# ProProject__CW32__2024-02-05.net
KiCad netlist of a schematic drawn in EasyEDA Pro
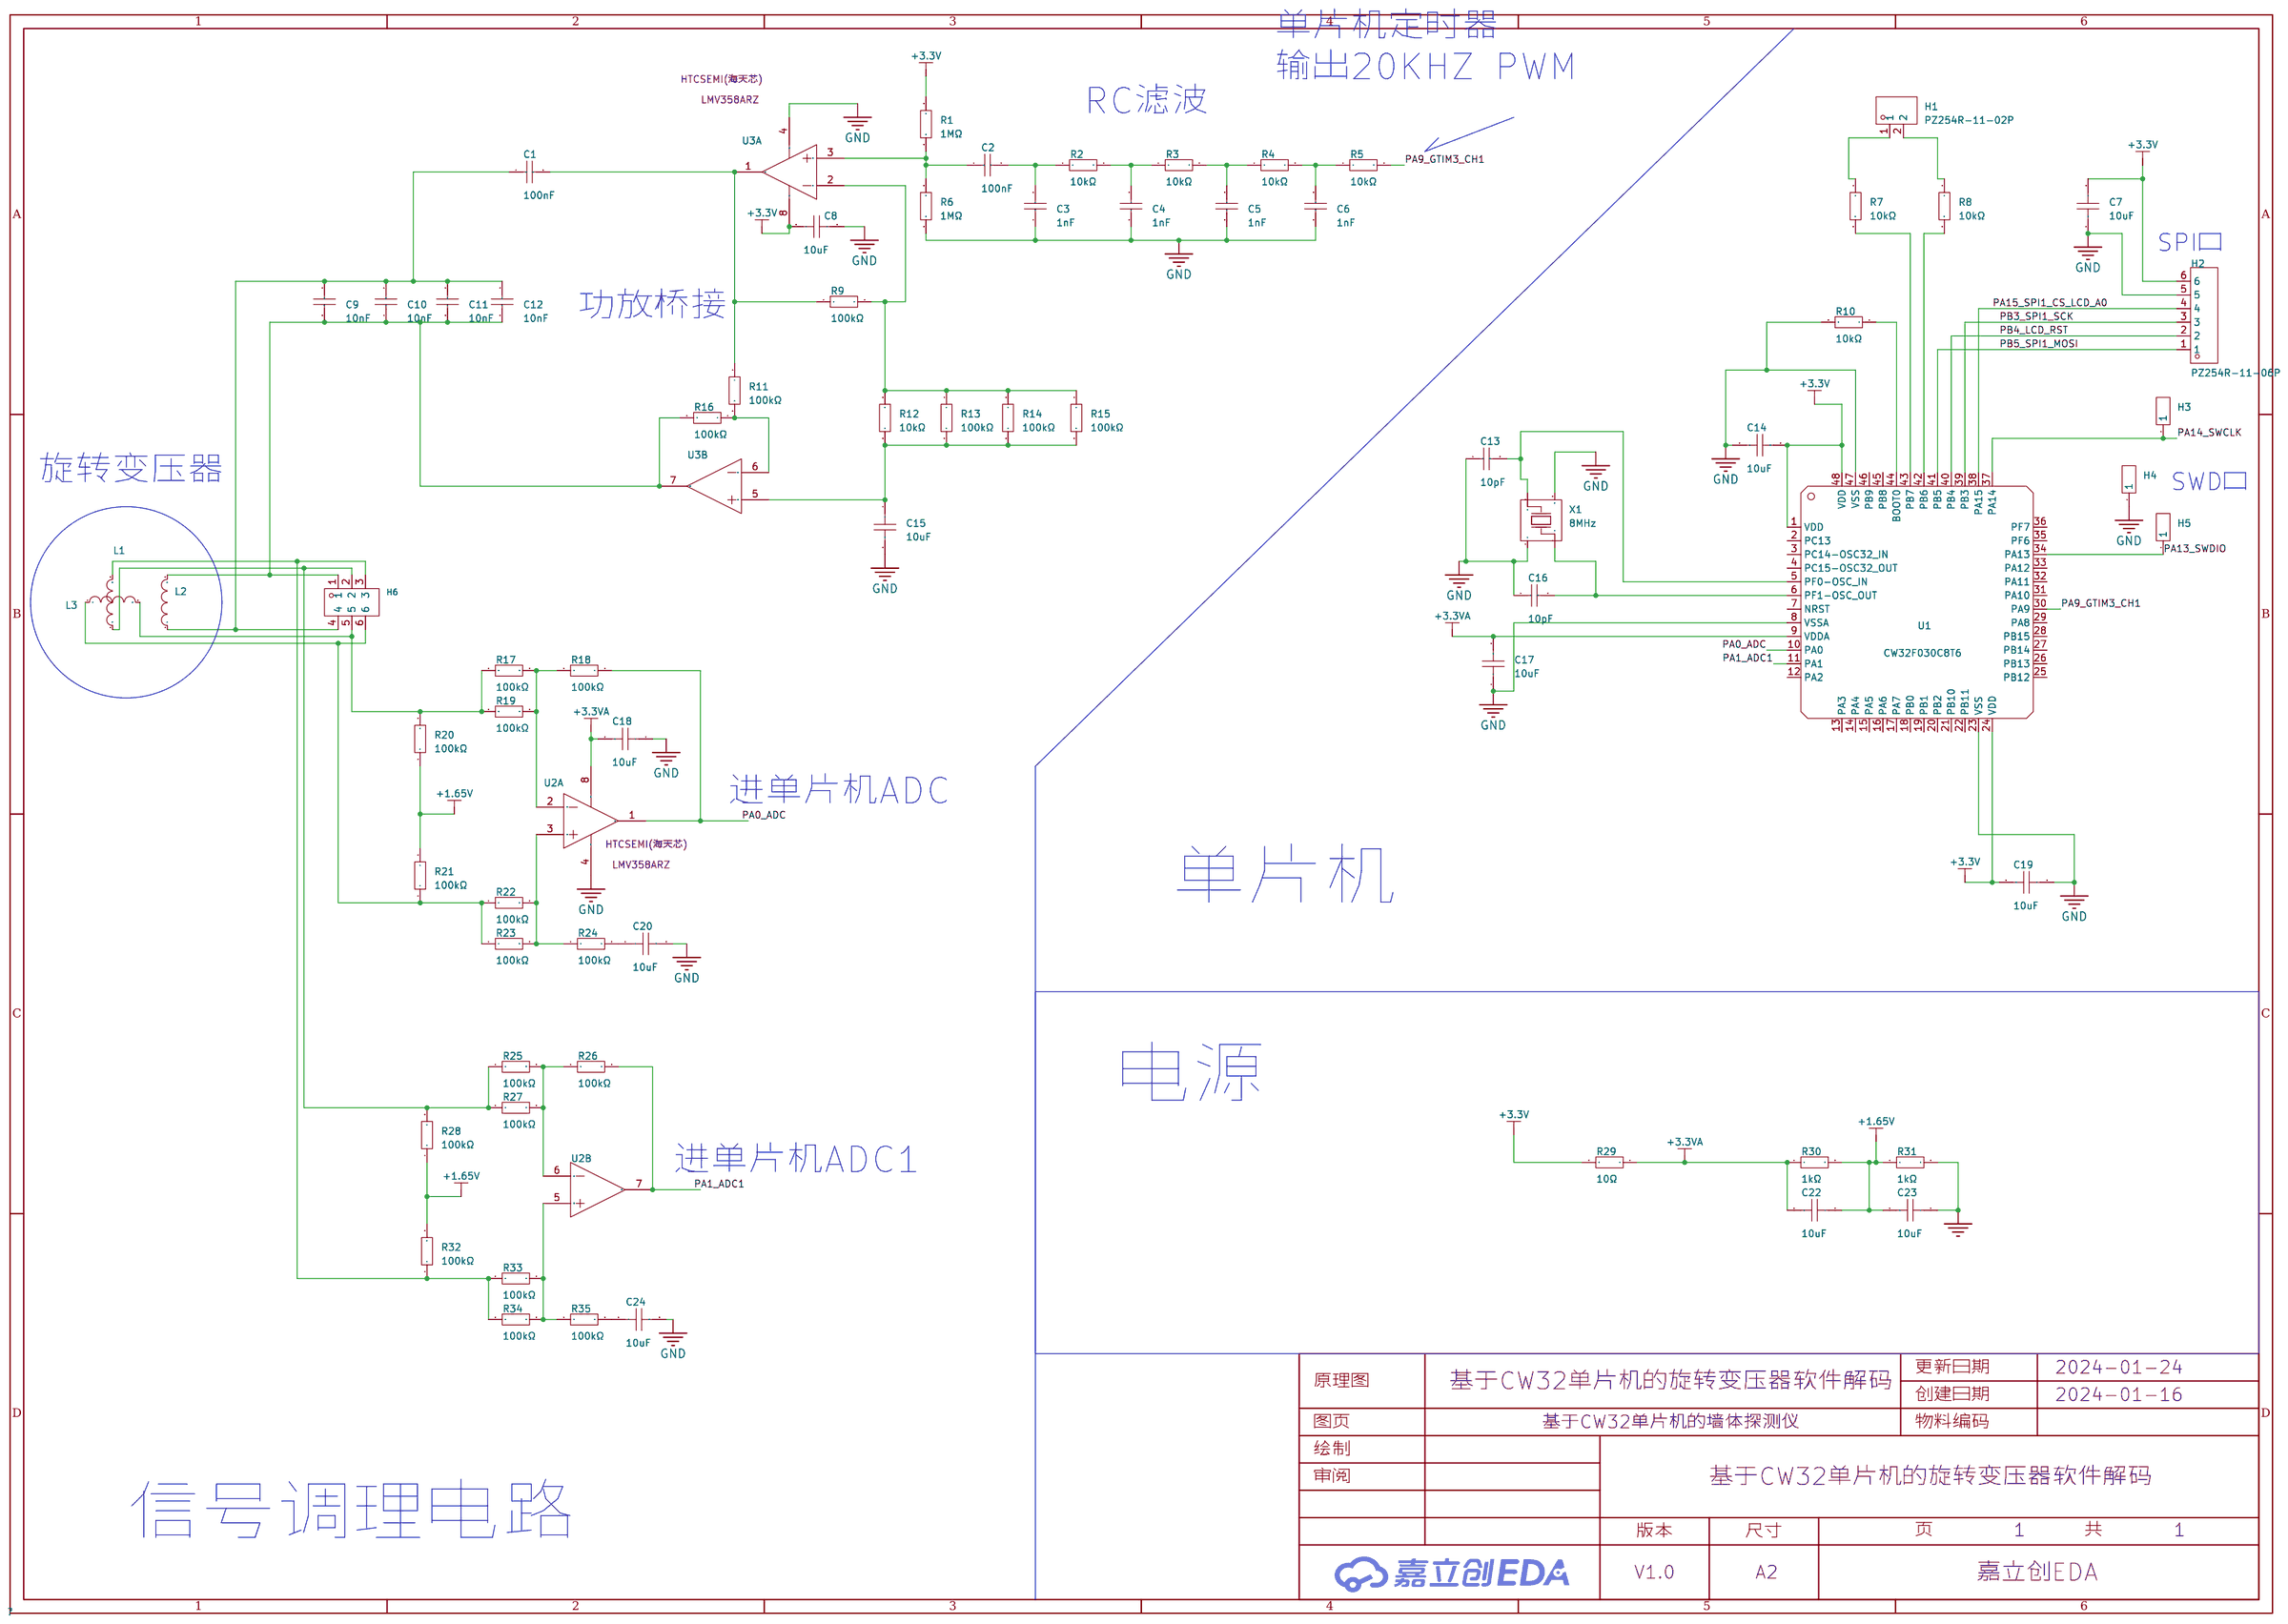
[diagram p0: schematic sheet]

(export (version "E")
  (design (tool "Eeschema 10.0.6"))
  (components
    (comp (ref "C1")
      (value "100nF")
      (footprint "easyedapro:C0603")
      (description "容值:100nF;精度:±10%;额定电压:50V;材质(温度系数):X7R;")
      (fields (field (name "Manufacturer Part") "0603B104K500NT") (field (name "Manufacturer") "FH(风华)"))
      (libsource (lib "easyedapro") (part "0603B104K500NT"))
    )
    (comp (ref "C2")
      (value "100nF")
      (footprint "easyedapro:C0603")
      (description "容值:100nF;精度:±10%;额定电压:50V;材质(温度系数):X7R;")
      (fields (field (name "Manufacturer Part") "0603B104K500NT") (field (name "Manufacturer") "FH(风华)"))
      (libsource (lib "easyedapro") (part "0603B104K500NT"))
    )
    (comp (ref "C3")
      (value "1nF")
      (footprint "easyedapro:C0603")
      (description "容值:1nF;精度:±5%;额定电压:50V;材质(温度系数):NP0;")
      (fields
        (field (name "Manufacturer Part") "CC0603JRNPO9BN102")
        (field (name "Manufacturer") "YAGEO(国巨)")
      )
      (libsource (lib "easyedapro") (part "CC0603JRNPO9BN102"))
    )
    (comp (ref "C4")
      (value "1nF")
      (footprint "easyedapro:C0603")
      (description "容值:1nF;精度:±5%;额定电压:50V;材质(温度系数):NP0;")
      (fields
        (field (name "Manufacturer Part") "CC0603JRNPO9BN102")
        (field (name "Manufacturer") "YAGEO(国巨)")
      )
      (libsource (lib "easyedapro") (part "CC0603JRNPO9BN102"))
    )
    (comp (ref "C5")
      (value "1nF")
      (footprint "easyedapro:C0603")
      (description "容值:1nF;精度:±5%;额定电压:50V;材质(温度系数):NP0;")
      (fields
        (field (name "Manufacturer Part") "CC0603JRNPO9BN102")
        (field (name "Manufacturer") "YAGEO(国巨)")
      )
      (libsource (lib "easyedapro") (part "CC0603JRNPO9BN102"))
    )
    (comp (ref "C6")
      (value "1nF")
      (footprint "easyedapro:C0603")
      (description "容值:1nF;精度:±5%;额定电压:50V;材质(温度系数):NP0;")
      (fields
        (field (name "Manufacturer Part") "CC0603JRNPO9BN102")
        (field (name "Manufacturer") "YAGEO(国巨)")
      )
      (libsource (lib "easyedapro") (part "CC0603JRNPO9BN102"))
    )
    (comp (ref "C7")
      (value "10uF")
      (footprint "easyedapro:C0603")
      (description "容值:10uF;精度:±10%;额定电压:10V;材质(温度系数):X5R;")
      (fields
        (field (name "Manufacturer Part") "CL10A106KP8NNNC")
        (field (name "Manufacturer") "SAMSUNG(三星)")
      )
      (libsource (lib "easyedapro") (part "CL10A106KP8NNNC"))
    )
    (comp (ref "C8")
      (value "10uF")
      (footprint "easyedapro:C0603")
      (description "容值:10uF;精度:±10%;额定电压:10V;材质(温度系数):X5R;")
      (fields
        (field (name "Manufacturer Part") "CL10A106KP8NNNC")
        (field (name "Manufacturer") "SAMSUNG(三星)")
      )
      (libsource (lib "easyedapro") (part "CL10A106KP8NNNC"))
    )
    (comp (ref "C9")
      (value "10nF")
      (footprint "easyedapro:C0603")
      (description "容值:10nF;精度:±10%;额定电压:50V;材质(温度系数):X7R;")
      (fields
        (field (name "Manufacturer Part") "CC0603KRX7R9BB103")
        (field (name "Manufacturer") "YAGEO(国巨)")
      )
      (libsource (lib "easyedapro") (part "CC0603KRX7R9BB103"))
    )
    (comp (ref "C10")
      (value "10nF")
      (footprint "easyedapro:C0603")
      (description "容值:10nF;精度:±10%;额定电压:50V;材质(温度系数):X7R;")
      (fields
        (field (name "Manufacturer Part") "CC0603KRX7R9BB103")
        (field (name "Manufacturer") "YAGEO(国巨)")
      )
      (libsource (lib "easyedapro") (part "CC0603KRX7R9BB103"))
    )
    (comp (ref "C11")
      (value "10nF")
      (footprint "easyedapro:C0603")
      (description "容值:10nF;精度:±10%;额定电压:50V;材质(温度系数):X7R;")
      (fields
        (field (name "Manufacturer Part") "CC0603KRX7R9BB103")
        (field (name "Manufacturer") "YAGEO(国巨)")
      )
      (libsource (lib "easyedapro") (part "CC0603KRX7R9BB103"))
    )
    (comp (ref "C12")
      (value "10nF")
      (footprint "easyedapro:C0603")
      (description "容值:10nF;精度:±10%;额定电压:50V;材质(温度系数):X7R;")
      (fields
        (field (name "Manufacturer Part") "CC0603KRX7R9BB103")
        (field (name "Manufacturer") "YAGEO(国巨)")
      )
      (libsource (lib "easyedapro") (part "CC0603KRX7R9BB103"))
    )
    (comp (ref "C13")
      (value "10pF")
      (footprint "easyedapro:C0603")
      (description "容值:10pF;精度:±5%;额定电压:50V;材质(温度系数):NP0;")
      (fields
        (field (name "Manufacturer Part") "CC0603JRNPO9BN100")
        (field (name "Manufacturer") "YAGEO(国巨)")
      )
      (libsource (lib "easyedapro") (part "CC0603JRNPO9BN100"))
    )
    (comp (ref "C14")
      (value "10uF")
      (footprint "easyedapro:C0603")
      (description "容值:10uF;精度:±10%;额定电压:10V;材质(温度系数):X5R;")
      (fields
        (field (name "Manufacturer Part") "CL10A106KP8NNNC")
        (field (name "Manufacturer") "SAMSUNG(三星)")
      )
      (libsource (lib "easyedapro") (part "CL10A106KP8NNNC"))
    )
    (comp (ref "C15")
      (value "10uF")
      (footprint "easyedapro:C0603")
      (description "容值:10uF;精度:±10%;额定电压:10V;材质(温度系数):X5R;")
      (fields
        (field (name "Manufacturer Part") "CL10A106KP8NNNC")
        (field (name "Manufacturer") "SAMSUNG(三星)")
      )
      (libsource (lib "easyedapro") (part "CL10A106KP8NNNC"))
    )
    (comp (ref "C16")
      (value "10pF")
      (footprint "easyedapro:C0603")
      (description "容值:10pF;精度:±5%;额定电压:50V;材质(温度系数):NP0;")
      (fields
        (field (name "Manufacturer Part") "CC0603JRNPO9BN100")
        (field (name "Manufacturer") "YAGEO(国巨)")
      )
      (libsource (lib "easyedapro") (part "CC0603JRNPO9BN100"))
    )
    (comp (ref "C17")
      (value "10uF")
      (footprint "easyedapro:C0603")
      (description "容值:10uF;精度:±10%;额定电压:10V;材质(温度系数):X5R;")
      (fields
        (field (name "Manufacturer Part") "CL10A106KP8NNNC")
        (field (name "Manufacturer") "SAMSUNG(三星)")
      )
      (libsource (lib "easyedapro") (part "CL10A106KP8NNNC"))
    )
    (comp (ref "C18")
      (value "10uF")
      (footprint "easyedapro:C0603")
      (description "容值:10uF;精度:±10%;额定电压:10V;材质(温度系数):X5R;")
      (fields
        (field (name "Manufacturer Part") "CL10A106KP8NNNC")
        (field (name "Manufacturer") "SAMSUNG(三星)")
      )
      (libsource (lib "easyedapro") (part "CL10A106KP8NNNC"))
    )
    (comp (ref "C19")
      (value "10uF")
      (footprint "easyedapro:C0603")
      (description "容值:10uF;精度:±10%;额定电压:10V;材质(温度系数):X5R;")
      (fields
        (field (name "Manufacturer Part") "CL10A106KP8NNNC")
        (field (name "Manufacturer") "SAMSUNG(三星)")
      )
      (libsource (lib "easyedapro") (part "CL10A106KP8NNNC"))
    )
    (comp (ref "C20")
      (value "10uF")
      (footprint "easyedapro:C0603")
      (description "容值:10uF;精度:±10%;额定电压:10V;材质(温度系数):X5R;")
      (fields
        (field (name "Manufacturer Part") "CL10A106KP8NNNC")
        (field (name "Manufacturer") "SAMSUNG(三星)")
      )
      (libsource (lib "easyedapro") (part "CL10A106KP8NNNC"))
    )
    (comp (ref "C22")
      (value "10uF")
      (footprint "easyedapro:C0603")
      (description "容值:10uF;精度:±10%;额定电压:10V;材质(温度系数):X5R;")
      (fields
        (field (name "Manufacturer Part") "CL10A106KP8NNNC")
        (field (name "Manufacturer") "SAMSUNG(三星)")
      )
      (libsource (lib "easyedapro") (part "CL10A106KP8NNNC"))
    )
    (comp (ref "C23")
      (value "10uF")
      (footprint "easyedapro:C0603")
      (description "容值:10uF;精度:±10%;额定电压:10V;材质(温度系数):X5R;")
      (fields
        (field (name "Manufacturer Part") "CL10A106KP8NNNC")
        (field (name "Manufacturer") "SAMSUNG(三星)")
      )
      (libsource (lib "easyedapro") (part "CL10A106KP8NNNC"))
    )
    (comp (ref "C24")
      (value "10uF")
      (footprint "easyedapro:C0603")
      (description "容值:10uF;精度:±10%;额定电压:10V;材质(温度系数):X5R;")
      (fields
        (field (name "Manufacturer Part") "CL10A106KP8NNNC")
        (field (name "Manufacturer") "SAMSUNG(三星)")
      )
      (libsource (lib "easyedapro") (part "CL10A106KP8NNNC"))
    )
    (comp (ref "H1")
      (value "PZ254R-11-02P")
      (footprint "easyedapro:HDR-TH_2P-P2.54-H-M-W10.4")
      (fields (field (name "Manufacturer") "XFCN(兴飞)"))
      (libsource (lib "easyedapro") (part "PZ254R-11-02P"))
    )
    (comp (ref "H2")
      (value "PZ254R-11-06P")
      (footprint "easyedapro:HDR-TH_6P-P2.54-H-M-W10.4")
      (fields (field (name "Manufacturer") "XFCN(兴飞)"))
      (libsource (lib "easyedapro") (part "PZ254R-11-06P"))
    )
    (comp (ref "H3")
      (value "~")
      (footprint "easyedapro:HDR-TH_1P-V-M_XKB_X4611WV-01I-C28D40")
      (libsource (lib "easyedapro") (part "HDR_1x1"))
    )
    (comp (ref "H4")
      (value "~")
      (footprint "easyedapro:HDR-TH_1P-V-M_XKB_X4611WV-01I-C28D40")
      (libsource (lib "easyedapro") (part "HDR_1x1"))
    )
    (comp (ref "H5")
      (value "~")
      (footprint "easyedapro:HDR-TH_1P-V-M_XKB_X4611WV-01I-C28D40")
      (libsource (lib "easyedapro") (part "HDR_1x1"))
    )
    (comp (ref "H6")
      (value "PZ254-2-03-Z-8.5")
      (footprint "easyedapro:HDR-TH_6P-P2.54-V-M-R2-C3-S2.54")
      (fields (field (name "Manufacturer") "HCTL(华灿天禄)"))
      (libsource (lib "easyedapro") (part "PZ254-2-03-Z-8.5"))
    )
    (comp (ref "L1")
      (value "10uH")
      (footprint "easyedapro:L1206")
      (libsource (lib "easyedapro") (part "CMI321609VR27KT"))
    )
    (comp (ref "L2")
      (value "6.3uH")
      (footprint "easyedapro:L1206")
      (libsource (lib "easyedapro") (part "CMI321609VR27KT"))
    )
    (comp (ref "L3")
      (value "10uH")
      (footprint "easyedapro:L1206")
      (libsource (lib "easyedapro") (part "CMI321609VR27KT"))
    )
    (comp (ref "R1")
      (value "1MΩ")
      (footprint "easyedapro:R0603")
      (description "电阻类型:厚膜电阻;阻值:1MΩ;精度:±1%;功率:100mW;")
      (fields
        (field (name "Manufacturer Part") "0603WAF1004T5E")
        (field (name "Manufacturer") "UNI-ROYAL(厚声)")
      )
      (libsource (lib "easyedapro") (part "0603WAF1004T5E"))
    )
    (comp (ref "R2")
      (value "10kΩ")
      (footprint "easyedapro:R0603")
      (description "电阻类型:厚膜电阻;阻值:10kΩ;精度:±1%;功率:100mW;")
      (fields (field (name "Manufacturer Part") "RC0603FR-0710KL") (field (name "Manufacturer") "YAGEO(国巨)"))
      (libsource (lib "easyedapro") (part "RC0603FR-0710KL"))
    )
    (comp (ref "R3")
      (value "10kΩ")
      (footprint "easyedapro:R0603")
      (description "电阻类型:厚膜电阻;阻值:10kΩ;精度:±1%;功率:100mW;")
      (fields (field (name "Manufacturer Part") "RC0603FR-0710KL") (field (name "Manufacturer") "YAGEO(国巨)"))
      (libsource (lib "easyedapro") (part "RC0603FR-0710KL"))
    )
    (comp (ref "R4")
      (value "10kΩ")
      (footprint "easyedapro:R0603")
      (description "电阻类型:厚膜电阻;阻值:10kΩ;精度:±1%;功率:100mW;")
      (fields (field (name "Manufacturer Part") "RC0603FR-0710KL") (field (name "Manufacturer") "YAGEO(国巨)"))
      (libsource (lib "easyedapro") (part "RC0603FR-0710KL"))
    )
    (comp (ref "R5")
      (value "10kΩ")
      (footprint "easyedapro:R0603")
      (description "电阻类型:厚膜电阻;阻值:10kΩ;精度:±1%;功率:100mW;")
      (fields (field (name "Manufacturer Part") "RC0603FR-0710KL") (field (name "Manufacturer") "YAGEO(国巨)"))
      (libsource (lib "easyedapro") (part "RC0603FR-0710KL"))
    )
    (comp (ref "R6")
      (value "1MΩ")
      (footprint "easyedapro:R0603")
      (description "电阻类型:厚膜电阻;阻值:1MΩ;精度:±1%;功率:100mW;")
      (fields
        (field (name "Manufacturer Part") "0603WAF1004T5E")
        (field (name "Manufacturer") "UNI-ROYAL(厚声)")
      )
      (libsource (lib "easyedapro") (part "0603WAF1004T5E"))
    )
    (comp (ref "R7")
      (value "10kΩ")
      (footprint "easyedapro:R0603")
      (description "电阻类型:厚膜电阻;阻值:10kΩ;精度:±1%;功率:100mW;")
      (fields (field (name "Manufacturer Part") "RC0603FR-0710KL") (field (name "Manufacturer") "YAGEO(国巨)"))
      (libsource (lib "easyedapro") (part "RC0603FR-0710KL"))
    )
    (comp (ref "R8")
      (value "10kΩ")
      (footprint "easyedapro:R0603")
      (description "电阻类型:厚膜电阻;阻值:10kΩ;精度:±1%;功率:100mW;")
      (fields (field (name "Manufacturer Part") "RC0603FR-0710KL") (field (name "Manufacturer") "YAGEO(国巨)"))
      (libsource (lib "easyedapro") (part "RC0603FR-0710KL"))
    )
    (comp (ref "R9")
      (value "100kΩ")
      (footprint "easyedapro:R0603")
      (description "电阻类型:厚膜电阻;阻值:100kΩ;精度:±1%;功率:100mW;")
      (fields (field (name "Manufacturer Part") "RC0603FR-07100KL") (field (name "Manufacturer") "YAGEO(国巨)"))
      (libsource (lib "easyedapro") (part "RC0603FR-07100KL"))
    )
    (comp (ref "R10")
      (value "10kΩ")
      (footprint "easyedapro:R0603")
      (description "电阻类型:厚膜电阻;阻值:10kΩ;精度:±1%;功率:100mW;")
      (fields (field (name "Manufacturer Part") "RC0603FR-0710KL") (field (name "Manufacturer") "YAGEO(国巨)"))
      (libsource (lib "easyedapro") (part "RC0603FR-0710KL"))
    )
    (comp (ref "R11")
      (value "100kΩ")
      (footprint "easyedapro:R0603")
      (description "电阻类型:厚膜电阻;阻值:100kΩ;精度:±1%;功率:100mW;")
      (fields (field (name "Manufacturer Part") "RC0603FR-07100KL") (field (name "Manufacturer") "YAGEO(国巨)"))
      (libsource (lib "easyedapro") (part "RC0603FR-07100KL"))
    )
    (comp (ref "R12")
      (value "10kΩ")
      (footprint "easyedapro:R0603")
      (description "电阻类型:厚膜电阻;阻值:10kΩ;精度:±1%;功率:100mW;")
      (fields (field (name "Manufacturer Part") "RC0603FR-0710KL") (field (name "Manufacturer") "YAGEO(国巨)"))
      (libsource (lib "easyedapro") (part "RC0603FR-0710KL"))
    )
    (comp (ref "R13")
      (value "100kΩ")
      (footprint "easyedapro:R0603")
      (description "电阻类型:厚膜电阻;阻值:100kΩ;精度:±1%;功率:100mW;")
      (fields (field (name "Manufacturer Part") "RC0603FR-07100KL") (field (name "Manufacturer") "YAGEO(国巨)"))
      (libsource (lib "easyedapro") (part "RC0603FR-07100KL"))
    )
    (comp (ref "R14")
      (value "100kΩ")
      (footprint "easyedapro:R0603")
      (description "电阻类型:厚膜电阻;阻值:100kΩ;精度:±1%;功率:100mW;")
      (fields (field (name "Manufacturer Part") "RC0603FR-07100KL") (field (name "Manufacturer") "YAGEO(国巨)"))
      (libsource (lib "easyedapro") (part "RC0603FR-07100KL"))
    )
    (comp (ref "R15")
      (value "100kΩ")
      (footprint "easyedapro:R0603")
      (description "电阻类型:厚膜电阻;阻值:100kΩ;精度:±1%;功率:100mW;")
      (fields (field (name "Manufacturer Part") "RC0603FR-07100KL") (field (name "Manufacturer") "YAGEO(国巨)"))
      (libsource (lib "easyedapro") (part "RC0603FR-07100KL"))
    )
    (comp (ref "R16")
      (value "100kΩ")
      (footprint "easyedapro:R0603")
      (description "电阻类型:厚膜电阻;阻值:100kΩ;精度:±1%;功率:100mW;")
      (fields (field (name "Manufacturer Part") "RC0603FR-07100KL") (field (name "Manufacturer") "YAGEO(国巨)"))
      (libsource (lib "easyedapro") (part "RC0603FR-07100KL"))
    )
    (comp (ref "R17")
      (value "100kΩ")
      (footprint "easyedapro:R0603")
      (description "电阻类型:厚膜电阻;阻值:100kΩ;精度:±1%;功率:100mW;")
      (fields (field (name "Manufacturer Part") "RC0603FR-07100KL") (field (name "Manufacturer") "YAGEO(国巨)"))
      (libsource (lib "easyedapro") (part "RC0603FR-07100KL"))
    )
    (comp (ref "R18")
      (value "100kΩ")
      (footprint "easyedapro:R0603")
      (description "电阻类型:厚膜电阻;阻值:100kΩ;精度:±1%;功率:100mW;")
      (fields (field (name "Manufacturer Part") "RC0603FR-07100KL") (field (name "Manufacturer") "YAGEO(国巨)"))
      (libsource (lib "easyedapro") (part "RC0603FR-07100KL"))
    )
    (comp (ref "R19")
      (value "100kΩ")
      (footprint "easyedapro:R0603")
      (description "电阻类型:厚膜电阻;阻值:100kΩ;精度:±1%;功率:100mW;")
      (fields (field (name "Manufacturer Part") "RC0603FR-07100KL") (field (name "Manufacturer") "YAGEO(国巨)"))
      (libsource (lib "easyedapro") (part "RC0603FR-07100KL"))
    )
    (comp (ref "R20")
      (value "100kΩ")
      (footprint "easyedapro:R0603")
      (description "电阻类型:厚膜电阻;阻值:100kΩ;精度:±1%;功率:100mW;")
      (fields (field (name "Manufacturer Part") "RC0603FR-07100KL") (field (name "Manufacturer") "YAGEO(国巨)"))
      (libsource (lib "easyedapro") (part "RC0603FR-07100KL"))
    )
    (comp (ref "R21")
      (value "100kΩ")
      (footprint "easyedapro:R0603")
      (description "电阻类型:厚膜电阻;阻值:100kΩ;精度:±1%;功率:100mW;")
      (fields (field (name "Manufacturer Part") "RC0603FR-07100KL") (field (name "Manufacturer") "YAGEO(国巨)"))
      (libsource (lib "easyedapro") (part "RC0603FR-07100KL"))
    )
    (comp (ref "R22")
      (value "100kΩ")
      (footprint "easyedapro:R0603")
      (description "电阻类型:厚膜电阻;阻值:100kΩ;精度:±1%;功率:100mW;")
      (fields (field (name "Manufacturer Part") "RC0603FR-07100KL") (field (name "Manufacturer") "YAGEO(国巨)"))
      (libsource (lib "easyedapro") (part "RC0603FR-07100KL"))
    )
    (comp (ref "R23")
      (value "100kΩ")
      (footprint "easyedapro:R0603")
      (description "电阻类型:厚膜电阻;阻值:100kΩ;精度:±1%;功率:100mW;")
      (fields (field (name "Manufacturer Part") "RC0603FR-07100KL") (field (name "Manufacturer") "YAGEO(国巨)"))
      (libsource (lib "easyedapro") (part "RC0603FR-07100KL"))
    )
    (comp (ref "R24")
      (value "100kΩ")
      (footprint "easyedapro:R0603")
      (description "电阻类型:厚膜电阻;阻值:100kΩ;精度:±1%;功率:100mW;")
      (fields (field (name "Manufacturer Part") "RC0603FR-07100KL") (field (name "Manufacturer") "YAGEO(国巨)"))
      (libsource (lib "easyedapro") (part "RC0603FR-07100KL"))
    )
    (comp (ref "R25")
      (value "100kΩ")
      (footprint "easyedapro:R0603")
      (description "电阻类型:厚膜电阻;阻值:100kΩ;精度:±1%;功率:100mW;")
      (fields (field (name "Manufacturer Part") "RC0603FR-07100KL") (field (name "Manufacturer") "YAGEO(国巨)"))
      (libsource (lib "easyedapro") (part "RC0603FR-07100KL"))
    )
    (comp (ref "R26")
      (value "100kΩ")
      (footprint "easyedapro:R0603")
      (description "电阻类型:厚膜电阻;阻值:100kΩ;精度:±1%;功率:100mW;")
      (fields (field (name "Manufacturer Part") "RC0603FR-07100KL") (field (name "Manufacturer") "YAGEO(国巨)"))
      (libsource (lib "easyedapro") (part "RC0603FR-07100KL"))
    )
    (comp (ref "R27")
      (value "100kΩ")
      (footprint "easyedapro:R0603")
      (description "电阻类型:厚膜电阻;阻值:100kΩ;精度:±1%;功率:100mW;")
      (fields (field (name "Manufacturer Part") "RC0603FR-07100KL") (field (name "Manufacturer") "YAGEO(国巨)"))
      (libsource (lib "easyedapro") (part "RC0603FR-07100KL"))
    )
    (comp (ref "R28")
      (value "100kΩ")
      (footprint "easyedapro:R0603")
      (description "电阻类型:厚膜电阻;阻值:100kΩ;精度:±1%;功率:100mW;")
      (fields (field (name "Manufacturer Part") "RC0603FR-07100KL") (field (name "Manufacturer") "YAGEO(国巨)"))
      (libsource (lib "easyedapro") (part "RC0603FR-07100KL"))
    )
    (comp (ref "R29")
      (value "10Ω")
      (footprint "easyedapro:R0603")
      (description "电阻类型:厚膜电阻;阻值:10Ω;精度:±1%;功率:100mW;")
      (fields
        (field (name "Manufacturer Part") "0603WAF100JT5E")
        (field (name "Manufacturer") "UNI-ROYAL(厚声)")
      )
      (libsource (lib "easyedapro") (part "0603WAF100JT5E"))
    )
    (comp (ref "R30")
      (value "1kΩ")
      (footprint "easyedapro:R0603")
      (description "电阻类型:厚膜电阻;阻值:1kΩ;精度:±1%;功率:100mW;")
      (fields (field (name "Manufacturer Part") "RC0603FR-071KL") (field (name "Manufacturer") "YAGEO(国巨)"))
      (libsource (lib "easyedapro") (part "RC0603FR-071KL"))
    )
    (comp (ref "R31")
      (value "1kΩ")
      (footprint "easyedapro:R0603")
      (description "电阻类型:厚膜电阻;阻值:1kΩ;精度:±1%;功率:100mW;")
      (fields (field (name "Manufacturer Part") "RC0603FR-071KL") (field (name "Manufacturer") "YAGEO(国巨)"))
      (libsource (lib "easyedapro") (part "RC0603FR-071KL"))
    )
    (comp (ref "R32")
      (value "100kΩ")
      (footprint "easyedapro:R0603")
      (description "电阻类型:厚膜电阻;阻值:100kΩ;精度:±1%;功率:100mW;")
      (fields (field (name "Manufacturer Part") "RC0603FR-07100KL") (field (name "Manufacturer") "YAGEO(国巨)"))
      (libsource (lib "easyedapro") (part "RC0603FR-07100KL"))
    )
    (comp (ref "R33")
      (value "100kΩ")
      (footprint "easyedapro:R0603")
      (description "电阻类型:厚膜电阻;阻值:100kΩ;精度:±1%;功率:100mW;")
      (fields (field (name "Manufacturer Part") "RC0603FR-07100KL") (field (name "Manufacturer") "YAGEO(国巨)"))
      (libsource (lib "easyedapro") (part "RC0603FR-07100KL"))
    )
    (comp (ref "R34")
      (value "100kΩ")
      (footprint "easyedapro:R0603")
      (description "电阻类型:厚膜电阻;阻值:100kΩ;精度:±1%;功率:100mW;")
      (fields (field (name "Manufacturer Part") "RC0603FR-07100KL") (field (name "Manufacturer") "YAGEO(国巨)"))
      (libsource (lib "easyedapro") (part "RC0603FR-07100KL"))
    )
    (comp (ref "R35")
      (value "100kΩ")
      (footprint "easyedapro:R0603")
      (description "电阻类型:厚膜电阻;阻值:100kΩ;精度:±1%;功率:100mW;")
      (fields (field (name "Manufacturer Part") "RC0603FR-07100KL") (field (name "Manufacturer") "YAGEO(国巨)"))
      (libsource (lib "easyedapro") (part "RC0603FR-07100KL"))
    )
    (comp (ref "U1")
      (value "CW32F030C8T6")
      (footprint "easyedapro:LQFP-48_L7.0-W7.0-P0.50-LS9.0-TL")
      (fields (field (name "Manufacturer") "CW(芯源)"))
      (libsource (lib "easyedapro") (part "CW32F030C8T6_C3019113"))
    )
    (comp (ref "U2")
      (value "{ManufacturerPart!}")
      (footprint "easyedapro:SOP-8_L4.9-W3.9-P1.27-LS6.0-BL")
      (description "CMOS低功耗双路运算放大器")
      (fields (field (name "Manufacturer Part") "LMV358ARZ") (field (name "Manufacturer") "HTCSEMI(海天芯)"))
      (libsource (lib "easyedapro") (part "LMV358ARZ"))
    )
    (comp (ref "U3")
      (value "{ManufacturerPart!}")
      (footprint "easyedapro:SOP-8_L4.9-W3.9-P1.27-LS6.0-BL")
      (description "CMOS低功耗双路运算放大器")
      (fields (field (name "Manufacturer Part") "LMV358ARZ") (field (name "Manufacturer") "HTCSEMI(海天芯)"))
      (libsource (lib "easyedapro") (part "LMV358ARZ"))
    )
    (comp (ref "X1")
      (value "8MHz")
      (footprint "easyedapro:OSC-SMD_4P-L3.2-W2.5-BL")
      (description "频率:8MHz;负载电容:10pF;频率公差:±10ppm;")
      (fields (field (name "Manufacturer Part") "TAXM8M4RDBCCT2T") (field (name "Manufacturer") "YJX(雅晶鑫)"))
      (libsource (lib "easyedapro") (part "TAXM8M4RDBCCT2T"))
    )
  )
  (nets
    (net (code "1") (name "+1.65V") (class "Default")
      (node (ref "C22") (pin "1") (pinfunction "1_1") (pintype "unspecified"))
      (node (ref "C23") (pin "2") (pinfunction "2_2") (pintype "unspecified"))
      (node (ref "R20") (pin "1") (pinfunction "1_1") (pintype "unspecified"))
      (node (ref "R21") (pin "2") (pinfunction "2_2") (pintype "unspecified"))
      (node (ref "R28") (pin "1") (pinfunction "1_1") (pintype "unspecified"))
      (node (ref "R30") (pin "2") (pinfunction "2_2") (pintype "input"))
      (node (ref "R31") (pin "1") (pinfunction "1_1") (pintype "input"))
      (node (ref "R32") (pin "2") (pinfunction "2_2") (pintype "unspecified"))
    )
    (net (code "2") (name "+3.3V") (class "Default")
      (node (ref "C14") (pin "2") (pinfunction "2_2") (pintype "unspecified"))
      (node (ref "C19") (pin "1") (pinfunction "1_1") (pintype "unspecified"))
      (node (ref "C7") (pin "2") (pinfunction "2_2") (pintype "unspecified"))
      (node (ref "C8") (pin "2") (pinfunction "2_2") (pintype "unspecified"))
      (node (ref "H2") (pin "6") (pinfunction "6_6") (pintype "unspecified"))
      (node (ref "R1") (pin "2") (pinfunction "2_2") (pintype "input"))
      (node (ref "R29") (pin "2") (pinfunction "2_2") (pintype "input"))
      (node (ref "U1") (pin "1") (pinfunction "VDD_1") (pintype "input"))
      (node (ref "U1") (pin "24") (pinfunction "VDD_24") (pintype "input"))
      (node (ref "U1") (pin "48") (pinfunction "VDD_48") (pintype "input"))
      (node (ref "U3") (pin "8") (pinfunction "VCC_8") (pintype "input"))
    )
    (net (code "3") (name "+3.3VA") (class "Default")
      (node (ref "C17") (pin "2") (pinfunction "2_2") (pintype "unspecified"))
      (node (ref "C18") (pin "2") (pinfunction "2_2") (pintype "unspecified"))
      (node (ref "C22") (pin "2") (pinfunction "2_2") (pintype "unspecified"))
      (node (ref "R29") (pin "1") (pinfunction "1_1") (pintype "input"))
      (node (ref "R30") (pin "1") (pinfunction "1_1") (pintype "input"))
      (node (ref "U1") (pin "9") (pinfunction "VDDA_9") (pintype "input"))
      (node (ref "U2") (pin "8") (pinfunction "VCC_8") (pintype "input"))
    )
    (net (code "4") (name "/PA0_ADC") (class "Default")
      (node (ref "R18") (pin "2") (pinfunction "2_2") (pintype "unspecified"))
      (node (ref "U1") (pin "10") (pinfunction "PA0_10") (pintype "input"))
      (node (ref "U2") (pin "1") (pinfunction "OUT_1") (pintype "output"))
    )
    (net (code "5") (name "/PA1_ADC1") (class "Default")
      (node (ref "R26") (pin "2") (pinfunction "2_2") (pintype "unspecified"))
      (node (ref "U1") (pin "11") (pinfunction "PA1_11") (pintype "input"))
      (node (ref "U2") (pin "7") (pinfunction "OUT2_7") (pintype "output"))
    )
    (net (code "6") (name "/PA9_GTIM3_CH1") (class "Default")
      (node (ref "R5") (pin "2") (pinfunction "2_2") (pintype "input"))
      (node (ref "U1") (pin "30") (pinfunction "PA9_30") (pintype "input"))
    )
    (net (code "7") (name "/PA13_SWDIO") (class "Default")
      (node (ref "H5") (pin "1") (pinfunction "1_1") (pintype "unspecified"))
      (node (ref "U1") (pin "34") (pinfunction "PA13_34") (pintype "input"))
    )
    (net (code "8") (name "/PA14_SWCLK") (class "Default")
      (node (ref "H3") (pin "1") (pinfunction "1_1") (pintype "unspecified"))
      (node (ref "U1") (pin "37") (pinfunction "PA14_37") (pintype "input"))
    )
    (net (code "9") (name "/PA15_SPI1_CS_LCD_A0") (class "Default")
      (node (ref "H2") (pin "4") (pinfunction "4_4") (pintype "unspecified"))
      (node (ref "U1") (pin "38") (pinfunction "PA15_38") (pintype "input"))
    )
    (net (code "10") (name "/PB3_SPI1_SCK") (class "Default")
      (node (ref "H2") (pin "3") (pinfunction "3_3") (pintype "unspecified"))
      (node (ref "U1") (pin "39") (pinfunction "PB3_39") (pintype "input"))
    )
    (net (code "11") (name "/PB4_LCD_RST") (class "Default")
      (node (ref "H2") (pin "2") (pinfunction "2_2") (pintype "unspecified"))
      (node (ref "U1") (pin "40") (pinfunction "PB4_40") (pintype "input"))
    )
    (net (code "12") (name "/PB5_SPI1_MOSI") (class "Default")
      (node (ref "H2") (pin "1") (pinfunction "1_1") (pintype "unspecified"))
      (node (ref "U1") (pin "41") (pinfunction "PB5_41") (pintype "input"))
    )
    (net (code "13") (name "GND") (class "Default")
      (node (ref "C13") (pin "1") (pinfunction "1_1") (pintype "input"))
      (node (ref "C14") (pin "1") (pinfunction "1_1") (pintype "unspecified"))
      (node (ref "C15") (pin "2") (pinfunction "2_2") (pintype "unspecified"))
      (node (ref "C16") (pin "1") (pinfunction "1_1") (pintype "input"))
      (node (ref "C17") (pin "1") (pinfunction "1_1") (pintype "unspecified"))
      (node (ref "C18") (pin "1") (pinfunction "1_1") (pintype "unspecified"))
      (node (ref "C19") (pin "2") (pinfunction "2_2") (pintype "unspecified"))
      (node (ref "C20") (pin "2") (pinfunction "2_2") (pintype "unspecified"))
      (node (ref "C23") (pin "1") (pinfunction "1_1") (pintype "unspecified"))
      (node (ref "C24") (pin "2") (pinfunction "2_2") (pintype "unspecified"))
      (node (ref "C3") (pin "1") (pinfunction "1_1") (pintype "input"))
      (node (ref "C4") (pin "1") (pinfunction "1_1") (pintype "input"))
      (node (ref "C5") (pin "1") (pinfunction "1_1") (pintype "input"))
      (node (ref "C6") (pin "1") (pinfunction "1_1") (pintype "input"))
      (node (ref "C7") (pin "1") (pinfunction "1_1") (pintype "unspecified"))
      (node (ref "C8") (pin "1") (pinfunction "1_1") (pintype "unspecified"))
      (node (ref "H2") (pin "5") (pinfunction "5_5") (pintype "unspecified"))
      (node (ref "H4") (pin "1") (pinfunction "1_1") (pintype "unspecified"))
      (node (ref "R10") (pin "2") (pinfunction "2_2") (pintype "input"))
      (node (ref "R31") (pin "2") (pinfunction "2_2") (pintype "input"))
      (node (ref "R6") (pin "1") (pinfunction "1_1") (pintype "input"))
      (node (ref "U1") (pin "23") (pinfunction "VSS_23") (pintype "input"))
      (node (ref "U1") (pin "47") (pinfunction "VSS_47") (pintype "input"))
      (node (ref "U1") (pin "8") (pinfunction "VSSA_8") (pintype "input"))
      (node (ref "U2") (pin "4") (pinfunction "GND_4") (pintype "input"))
      (node (ref "U3") (pin "4") (pinfunction "GND_4") (pintype "input"))
      (node (ref "X1") (pin "2") (pinfunction "2_2") (pintype "input"))
      (node (ref "X1") (pin "4") (pinfunction "4_4") (pintype "input"))
    )
    (net (code "14") (name "Net-(C1-Pad1)") (class "Default")
      (node (ref "C1") (pin "1") (pinfunction "1_1") (pintype "input"))
      (node (ref "C10") (pin "2") (pinfunction "2_2") (pintype "input"))
      (node (ref "C11") (pin "2") (pinfunction "2_2") (pintype "input"))
      (node (ref "C12") (pin "2") (pinfunction "2_2") (pintype "input"))
      (node (ref "C9") (pin "2") (pinfunction "2_2") (pintype "input"))
      (node (ref "H6") (pin "4") (pinfunction "4_4") (pintype "input"))
      (node (ref "L2") (pin "1") (pinfunction "1_1") (pintype "input"))
    )
    (net (code "15") (name "Net-(C2-Pad2)") (class "Default")
      (node (ref "C2") (pin "2") (pinfunction "2_2") (pintype "input"))
      (node (ref "C3") (pin "2") (pinfunction "2_2") (pintype "input"))
      (node (ref "R2") (pin "1") (pinfunction "1_1") (pintype "input"))
    )
    (net (code "16") (name "Net-(C4-Pad2)") (class "Default")
      (node (ref "C4") (pin "2") (pinfunction "2_2") (pintype "input"))
      (node (ref "R2") (pin "2") (pinfunction "2_2") (pintype "input"))
      (node (ref "R3") (pin "1") (pinfunction "1_1") (pintype "input"))
    )
    (net (code "17") (name "Net-(C5-Pad2)") (class "Default")
      (node (ref "C5") (pin "2") (pinfunction "2_2") (pintype "input"))
      (node (ref "R3") (pin "2") (pinfunction "2_2") (pintype "input"))
      (node (ref "R4") (pin "1") (pinfunction "1_1") (pintype "input"))
    )
    (net (code "18") (name "Net-(C6-Pad2)") (class "Default")
      (node (ref "C6") (pin "2") (pinfunction "2_2") (pintype "input"))
      (node (ref "R4") (pin "2") (pinfunction "2_2") (pintype "input"))
      (node (ref "R5") (pin "1") (pinfunction "1_1") (pintype "input"))
    )
    (net (code "19") (name "Net-(C20-Pad1)") (class "Default")
      (node (ref "C20") (pin "1") (pinfunction "1_1") (pintype "unspecified"))
      (node (ref "R24") (pin "2") (pinfunction "2_2") (pintype "unspecified"))
    )
    (net (code "20") (name "Net-(C24-Pad1)") (class "Default")
      (node (ref "C24") (pin "1") (pinfunction "1_1") (pintype "unspecified"))
      (node (ref "R35") (pin "2") (pinfunction "2_2") (pintype "unspecified"))
    )
    (net (code "21") (name "Net-(H1-Pad1)") (class "Default")
      (node (ref "H1") (pin "1") (pinfunction "1_1") (pintype "unspecified"))
      (node (ref "R7") (pin "1") (pinfunction "1_1") (pintype "input"))
    )
    (net (code "22") (name "Net-(H1-Pad2)") (class "Default")
      (node (ref "H1") (pin "2") (pinfunction "2_2") (pintype "unspecified"))
      (node (ref "R8") (pin "1") (pinfunction "1_1") (pintype "input"))
    )
    (net (code "23") (name "Net-(H6-Pad2)") (class "Default")
      (node (ref "H6") (pin "2") (pinfunction "2_2") (pintype "input"))
      (node (ref "L1") (pin "1") (pinfunction "1_1") (pintype "input"))
      (node (ref "R25") (pin "1") (pinfunction "1_1") (pintype "unspecified"))
      (node (ref "R27") (pin "1") (pinfunction "1_1") (pintype "unspecified"))
      (node (ref "R28") (pin "2") (pinfunction "2_2") (pintype "unspecified"))
    )
    (net (code "24") (name "Net-(H6-Pad3)") (class "Default")
      (node (ref "H6") (pin "3") (pinfunction "3_3") (pintype "input"))
      (node (ref "L1") (pin "2") (pinfunction "2_2") (pintype "input"))
      (node (ref "R32") (pin "1") (pinfunction "1_1") (pintype "unspecified"))
      (node (ref "R33") (pin "1") (pinfunction "1_1") (pintype "unspecified"))
      (node (ref "R34") (pin "1") (pinfunction "1_1") (pintype "unspecified"))
    )
    (net (code "25") (name "Net-(H6-Pad5)") (class "Default")
      (node (ref "H6") (pin "5") (pinfunction "5_5") (pintype "input"))
      (node (ref "L3") (pin "2") (pinfunction "2_2") (pintype "input"))
      (node (ref "R17") (pin "1") (pinfunction "1_1") (pintype "unspecified"))
      (node (ref "R19") (pin "1") (pinfunction "1_1") (pintype "unspecified"))
      (node (ref "R20") (pin "2") (pinfunction "2_2") (pintype "unspecified"))
    )
    (net (code "26") (name "Net-(H6-Pad6)") (class "Default")
      (node (ref "H6") (pin "6") (pinfunction "6_6") (pintype "input"))
      (node (ref "L3") (pin "1") (pinfunction "1_1") (pintype "input"))
      (node (ref "R21") (pin "1") (pinfunction "1_1") (pintype "unspecified"))
      (node (ref "R22") (pin "1") (pinfunction "1_1") (pintype "unspecified"))
      (node (ref "R23") (pin "1") (pinfunction "1_1") (pintype "unspecified"))
    )
    (net (code "27") (name "Net-(U1-BOOT0)") (class "Default")
      (node (ref "R10") (pin "1") (pinfunction "1_1") (pintype "input"))
      (node (ref "U1") (pin "44") (pinfunction "BOOT0_44") (pintype "input"))
    )
    (net (code "28") (name "Net-(U1-PB6)") (class "Default")
      (node (ref "R8") (pin "2") (pinfunction "2_2") (pintype "input"))
      (node (ref "U1") (pin "42") (pinfunction "PB6_42") (pintype "input"))
    )
    (net (code "29") (name "Net-(U1-PB7)") (class "Default")
      (node (ref "R7") (pin "2") (pinfunction "2_2") (pintype "input"))
      (node (ref "U1") (pin "43") (pinfunction "PB7_43") (pintype "input"))
    )
    (net (code "30") (name "Net-(U1-PF0-OSC_IN)") (class "Default")
      (node (ref "C13") (pin "2") (pinfunction "2_2") (pintype "input"))
      (node (ref "U1") (pin "5") (pinfunction "PF0-OSC_IN_5") (pintype "input"))
      (node (ref "X1") (pin "3") (pinfunction "3_3") (pintype "input"))
    )
    (net (code "31") (name "Net-(U1-PF1-OSC_OUT)") (class "Default")
      (node (ref "C16") (pin "2") (pinfunction "2_2") (pintype "input"))
      (node (ref "U1") (pin "6") (pinfunction "PF1-OSC_OUT_6") (pintype "input"))
      (node (ref "X1") (pin "1") (pinfunction "1_1") (pintype "input"))
    )
    (net (code "32") (name "Net-(U2A-IN1+)") (class "Default")
      (node (ref "R22") (pin "2") (pinfunction "2_2") (pintype "unspecified"))
      (node (ref "R23") (pin "2") (pinfunction "2_2") (pintype "unspecified"))
      (node (ref "R24") (pin "1") (pinfunction "1_1") (pintype "unspecified"))
      (node (ref "U2") (pin "3") (pinfunction "IN1+_3") (pintype "input"))
    )
    (net (code "33") (name "Net-(U2A-IN1-)") (class "Default")
      (node (ref "R17") (pin "2") (pinfunction "2_2") (pintype "unspecified"))
      (node (ref "R18") (pin "1") (pinfunction "1_1") (pintype "unspecified"))
      (node (ref "R19") (pin "2") (pinfunction "2_2") (pintype "unspecified"))
      (node (ref "U2") (pin "2") (pinfunction "IN1-_2") (pintype "input"))
    )
    (net (code "34") (name "Net-(U2B-IN2+)") (class "Default")
      (node (ref "R33") (pin "2") (pinfunction "2_2") (pintype "unspecified"))
      (node (ref "R34") (pin "2") (pinfunction "2_2") (pintype "unspecified"))
      (node (ref "R35") (pin "1") (pinfunction "1_1") (pintype "unspecified"))
      (node (ref "U2") (pin "5") (pinfunction "IN2+_5") (pintype "input"))
    )
    (net (code "35") (name "Net-(U2B-IN2-)") (class "Default")
      (node (ref "R25") (pin "2") (pinfunction "2_2") (pintype "unspecified"))
      (node (ref "R26") (pin "1") (pinfunction "1_1") (pintype "unspecified"))
      (node (ref "R27") (pin "2") (pinfunction "2_2") (pintype "unspecified"))
      (node (ref "U2") (pin "6") (pinfunction "IN2-_6") (pintype "input"))
    )
    (net (code "36") (name "Net-(U3A-IN1+)") (class "Default")
      (node (ref "C2") (pin "1") (pinfunction "1_1") (pintype "input"))
      (node (ref "R1") (pin "1") (pinfunction "1_1") (pintype "input"))
      (node (ref "R6") (pin "2") (pinfunction "2_2") (pintype "input"))
      (node (ref "U3") (pin "3") (pinfunction "IN1+_3") (pintype "input"))
    )
    (net (code "37") (name "Net-(U3A-IN1-)") (class "Default")
      (node (ref "R12") (pin "2") (pinfunction "2_2") (pintype "input"))
      (node (ref "R13") (pin "1") (pinfunction "1_1") (pintype "unspecified"))
      (node (ref "R14") (pin "1") (pinfunction "1_1") (pintype "unspecified"))
      (node (ref "R15") (pin "1") (pinfunction "1_1") (pintype "unspecified"))
      (node (ref "R9") (pin "2") (pinfunction "2_2") (pintype "unspecified"))
      (node (ref "U3") (pin "2") (pinfunction "IN1-_2") (pintype "input"))
    )
    (net (code "38") (name "Net-(U3A-OUT)") (class "Default")
      (node (ref "C1") (pin "2") (pinfunction "2_2") (pintype "input"))
      (node (ref "R11") (pin "1") (pinfunction "1_1") (pintype "unspecified"))
      (node (ref "R9") (pin "1") (pinfunction "1_1") (pintype "unspecified"))
      (node (ref "U3") (pin "1") (pinfunction "OUT_1") (pintype "output"))
    )
    (net (code "39") (name "Net-(U3B-IN2+)") (class "Default")
      (node (ref "C15") (pin "1") (pinfunction "1_1") (pintype "unspecified"))
      (node (ref "R12") (pin "1") (pinfunction "1_1") (pintype "input"))
      (node (ref "R13") (pin "2") (pinfunction "2_2") (pintype "unspecified"))
      (node (ref "R14") (pin "2") (pinfunction "2_2") (pintype "unspecified"))
      (node (ref "R15") (pin "2") (pinfunction "2_2") (pintype "unspecified"))
      (node (ref "U3") (pin "5") (pinfunction "IN2+_5") (pintype "input"))
    )
    (net (code "40") (name "Net-(U3B-IN2-)") (class "Default")
      (node (ref "R11") (pin "2") (pinfunction "2_2") (pintype "unspecified"))
      (node (ref "R16") (pin "1") (pinfunction "1_1") (pintype "unspecified"))
      (node (ref "U3") (pin "6") (pinfunction "IN2-_6") (pintype "input"))
    )
    (net (code "41") (name "Net-(U3B-OUT2)") (class "Default")
      (node (ref "C10") (pin "1") (pinfunction "1_1") (pintype "input"))
      (node (ref "C11") (pin "1") (pinfunction "1_1") (pintype "input"))
      (node (ref "C12") (pin "1") (pinfunction "1_1") (pintype "input"))
      (node (ref "C9") (pin "1") (pinfunction "1_1") (pintype "input"))
      (node (ref "H6") (pin "1") (pinfunction "1_1") (pintype "input"))
      (node (ref "L2") (pin "2") (pinfunction "2_2") (pintype "input"))
      (node (ref "R16") (pin "2") (pinfunction "2_2") (pintype "unspecified"))
      (node (ref "U3") (pin "7") (pinfunction "OUT2_7") (pintype "output"))
    )
    (net (code "42") (name "unconnected-(U1-NRST-Pad7)") (class "Default")
      (node (ref "U1") (pin "7") (pinfunction "NRST_7") (pintype "input"))
    )
    (net (code "43") (name "unconnected-(U1-PA2-Pad12)") (class "Default")
      (node (ref "U1") (pin "12") (pinfunction "PA2_12") (pintype "input"))
    )
    (net (code "44") (name "unconnected-(U1-PA3-Pad13)") (class "Default")
      (node (ref "U1") (pin "13") (pinfunction "PA3_13") (pintype "input"))
    )
    (net (code "45") (name "unconnected-(U1-PA4-Pad14)") (class "Default")
      (node (ref "U1") (pin "14") (pinfunction "PA4_14") (pintype "input"))
    )
    (net (code "46") (name "unconnected-(U1-PA5-Pad15)") (class "Default")
      (node (ref "U1") (pin "15") (pinfunction "PA5_15") (pintype "input"))
    )
    (net (code "47") (name "unconnected-(U1-PA6-Pad16)") (class "Default")
      (node (ref "U1") (pin "16") (pinfunction "PA6_16") (pintype "input"))
    )
    (net (code "48") (name "unconnected-(U1-PA7-Pad17)") (class "Default")
      (node (ref "U1") (pin "17") (pinfunction "PA7_17") (pintype "input"))
    )
    (net (code "49") (name "unconnected-(U1-PA8-Pad29)") (class "Default")
      (node (ref "U1") (pin "29") (pinfunction "PA8_29") (pintype "input"))
    )
    (net (code "50") (name "unconnected-(U1-PA10-Pad31)") (class "Default")
      (node (ref "U1") (pin "31") (pinfunction "PA10_31") (pintype "input"))
    )
    (net (code "51") (name "unconnected-(U1-PA11-Pad32)") (class "Default")
      (node (ref "U1") (pin "32") (pinfunction "PA11_32") (pintype "input"))
    )
    (net (code "52") (name "unconnected-(U1-PA12-Pad33)") (class "Default")
      (node (ref "U1") (pin "33") (pinfunction "PA12_33") (pintype "input"))
    )
    (net (code "53") (name "unconnected-(U1-PB0-Pad18)") (class "Default")
      (node (ref "U1") (pin "18") (pinfunction "PB0_18") (pintype "input"))
    )
    (net (code "54") (name "unconnected-(U1-PB1-Pad19)") (class "Default")
      (node (ref "U1") (pin "19") (pinfunction "PB1_19") (pintype "input"))
    )
    (net (code "55") (name "unconnected-(U1-PB2-Pad20)") (class "Default")
      (node (ref "U1") (pin "20") (pinfunction "PB2_20") (pintype "input"))
    )
    (net (code "56") (name "unconnected-(U1-PB8-Pad45)") (class "Default")
      (node (ref "U1") (pin "45") (pinfunction "PB8_45") (pintype "input"))
    )
    (net (code "57") (name "unconnected-(U1-PB9-Pad46)") (class "Default")
      (node (ref "U1") (pin "46") (pinfunction "PB9_46") (pintype "input"))
    )
    (net (code "58") (name "unconnected-(U1-PB10-Pad21)") (class "Default")
      (node (ref "U1") (pin "21") (pinfunction "PB10_21") (pintype "input"))
    )
    (net (code "59") (name "unconnected-(U1-PB11-Pad22)") (class "Default")
      (node (ref "U1") (pin "22") (pinfunction "PB11_22") (pintype "input"))
    )
    (net (code "60") (name "unconnected-(U1-PB12-Pad25)") (class "Default")
      (node (ref "U1") (pin "25") (pinfunction "PB12_25") (pintype "input"))
    )
    (net (code "61") (name "unconnected-(U1-PB13-Pad26)") (class "Default")
      (node (ref "U1") (pin "26") (pinfunction "PB13_26") (pintype "input"))
    )
    (net (code "62") (name "unconnected-(U1-PB14-Pad27)") (class "Default")
      (node (ref "U1") (pin "27") (pinfunction "PB14_27") (pintype "input"))
    )
    (net (code "63") (name "unconnected-(U1-PB15-Pad28)") (class "Default")
      (node (ref "U1") (pin "28") (pinfunction "PB15_28") (pintype "input"))
    )
    (net (code "64") (name "unconnected-(U1-PC13-Pad2)") (class "Default")
      (node (ref "U1") (pin "2") (pinfunction "PC13_2") (pintype "input"))
    )
    (net (code "65") (name "unconnected-(U1-PC14-OSC32_IN-Pad3)") (class "Default")
      (node (ref "U1") (pin "3") (pinfunction "PC14-OSC32_IN_3") (pintype "input"))
    )
    (net (code "66") (name "unconnected-(U1-PC15-OSC32_OUT-Pad4)") (class "Default")
      (node (ref "U1") (pin "4") (pinfunction "PC15-OSC32_OUT_4") (pintype "input"))
    )
    (net (code "67") (name "unconnected-(U1-PF6-Pad35)") (class "Default")
      (node (ref "U1") (pin "35") (pinfunction "PF6_35") (pintype "input"))
    )
    (net (code "68") (name "unconnected-(U1-PF7-Pad36)") (class "Default")
      (node (ref "U1") (pin "36") (pinfunction "PF7_36") (pintype "input"))
    )
  )
)
